# 8161_-FSK_V2_0.net
KiCad netlist of a schematic drawn in Altium Designer
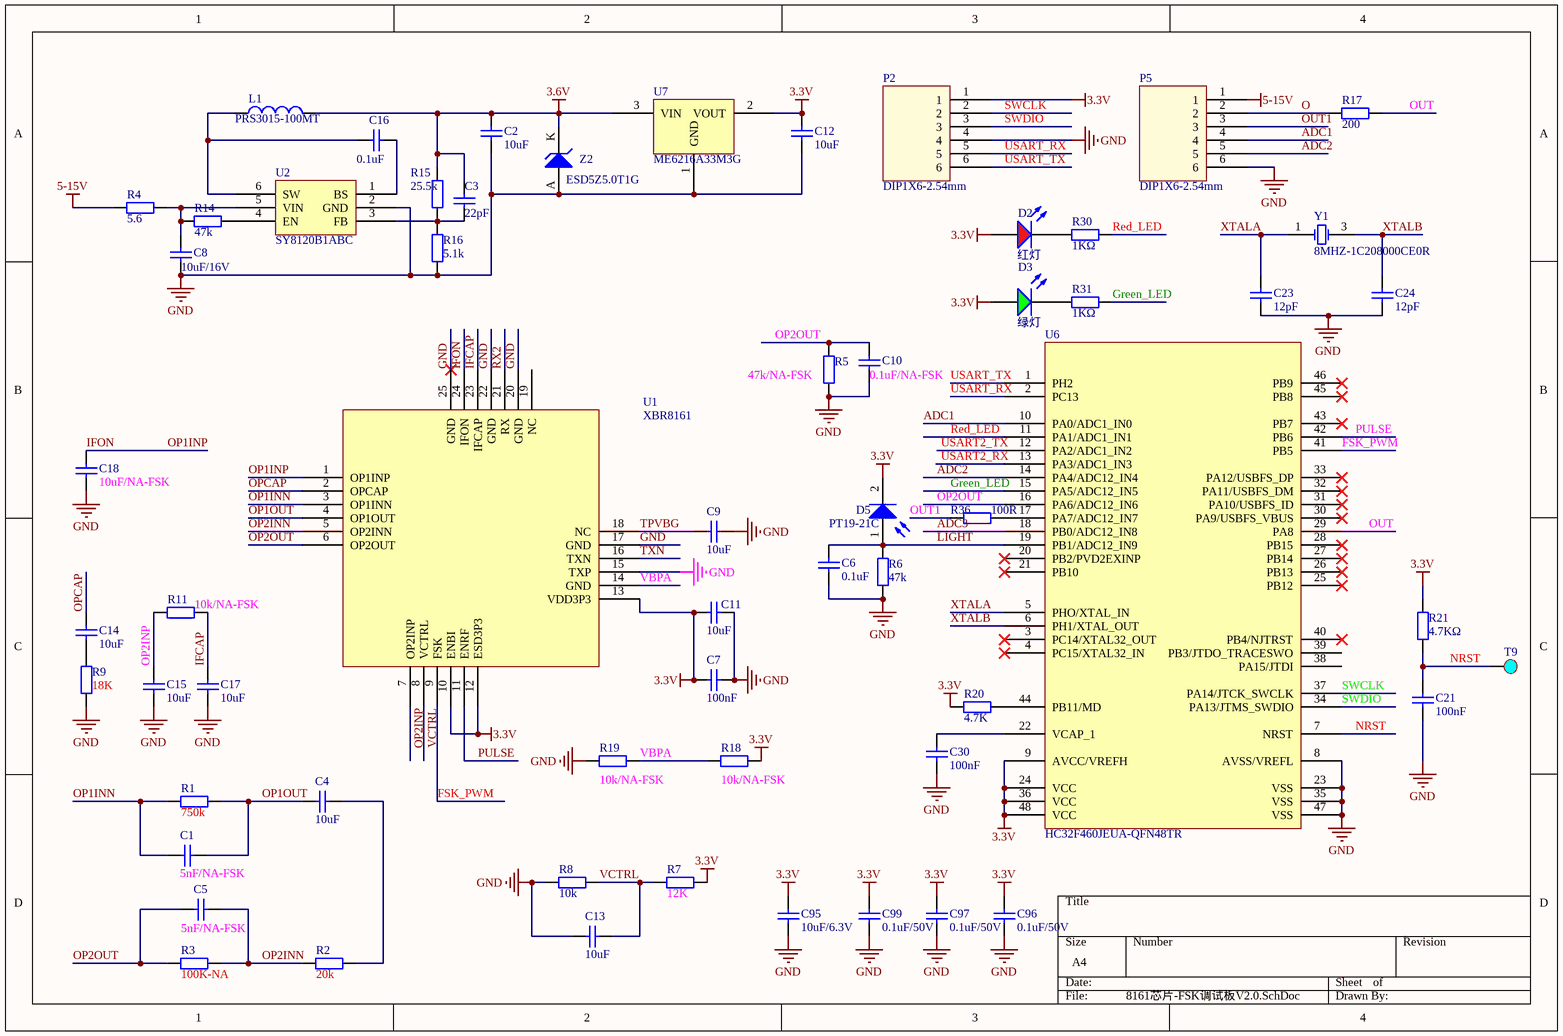
[diagram p0: 8161芯片-FSK调试板V2.0.SchDoc]

(export (version "E")
  (design (tool "Eeschema 10.0.6"))
  (components
    (comp (ref "C1")
      (value "5nF/NA-FSK")
      (footprint "C0402")
      (description "Capacitor")
      (fields (field (name "PUBLISHER") "Altium Limited"))
      (libsource (lib "Miscellaneous Devices") (part "Cap"))
    )
    (comp (ref "C2")
      (value "10uF")
      (footprint "C0402")
      (description "Capacitor")
      (fields (field (name "PUBLISHER") "Altium Limited"))
      (libsource (lib "Miscellaneous Devices") (part "Cap"))
    )
    (comp (ref "C3")
      (value "22pF")
      (footprint "C0402")
      (description "Capacitor")
      (fields (field (name "PUBLISHER") "Altium Limited"))
      (libsource (lib "Miscellaneous Devices") (part "Cap"))
    )
    (comp (ref "C4")
      (value "10uF")
      (footprint "C0402")
      (description "Capacitor")
      (fields (field (name "PUBLISHER") "Altium Limited"))
      (libsource (lib "Miscellaneous Devices") (part "Cap"))
    )
    (comp (ref "C5")
      (value "5nF/NA-FSK")
      (footprint "C0402")
      (description "Capacitor")
      (fields (field (name "PUBLISHER") "Altium Limited"))
      (libsource (lib "Miscellaneous Devices") (part "Cap"))
    )
    (comp (ref "C6")
      (value "0.1uF")
      (footprint "C0402")
      (description "Capacitor")
      (fields (field (name "PUBLISHER") "Altium Limited"))
      (libsource (lib "Miscellaneous Devices") (part "Cap"))
    )
    (comp (ref "C7")
      (value "100nF")
      (footprint "C0402")
      (description "Capacitor")
      (fields (field (name "PUBLISHER") "Altium Limited"))
      (libsource (lib "Miscellaneous Devices") (part "Cap"))
    )
    (comp (ref "C8")
      (value "10uF/16V")
      (footprint "C0603")
      (description "Capacitor")
      (fields (field (name "PUBLISHER") "Altium Limited"))
      (libsource (lib "Miscellaneous Devices") (part "Cap"))
    )
    (comp (ref "C9")
      (value "10uF")
      (footprint "C0402")
      (description "Capacitor")
      (fields (field (name "PUBLISHER") "Altium Limited"))
      (libsource (lib "Miscellaneous Devices") (part "Cap"))
    )
    (comp (ref "C10")
      (value "0.1uF/NA-FSK")
      (footprint "C0402")
      (description "Capacitor")
      (fields (field (name "PUBLISHER") "Altium Limited"))
      (libsource (lib "Miscellaneous Devices") (part "Cap"))
    )
    (comp (ref "C11")
      (value "10uF")
      (footprint "C0402")
      (description "Capacitor")
      (fields (field (name "PUBLISHER") "Altium Limited"))
      (libsource (lib "Miscellaneous Devices") (part "Cap"))
    )
    (comp (ref "C12")
      (value "10uF")
      (footprint "C0402")
      (description "Capacitor")
      (fields (field (name "PUBLISHER") "Altium Limited"))
      (libsource (lib "Miscellaneous Devices") (part "Cap"))
    )
    (comp (ref "C13")
      (value "10uF")
      (footprint "C0402")
      (description "Capacitor")
      (fields (field (name "PUBLISHER") "Altium Limited"))
      (libsource (lib "Miscellaneous Devices") (part "Cap"))
    )
    (comp (ref "C14")
      (value "10uF")
      (footprint "C0402")
      (description "Capacitor")
      (fields (field (name "PUBLISHER") "Altium Limited"))
      (libsource (lib "Miscellaneous Devices") (part "Cap"))
    )
    (comp (ref "C15")
      (value "10uF")
      (footprint "C0402")
      (description "Capacitor")
      (fields (field (name "PUBLISHER") "Altium Limited"))
      (libsource (lib "Miscellaneous Devices") (part "Cap"))
    )
    (comp (ref "C16")
      (value "0.1uF")
      (footprint "C0402")
      (description "Capacitor")
      (fields (field (name "PUBLISHER") "Altium Limited"))
      (libsource (lib "Miscellaneous Devices") (part "Cap"))
    )
    (comp (ref "C17")
      (value "10uF")
      (footprint "C0402")
      (description "Capacitor")
      (fields (field (name "PUBLISHER") "Altium Limited"))
      (libsource (lib "Miscellaneous Devices") (part "Cap"))
    )
    (comp (ref "C18")
      (value "10uF/NA-FSK")
      (footprint "C0402")
      (description "Capacitor")
      (fields (field (name "PUBLISHER") "Altium Limited"))
      (libsource (lib "Miscellaneous Devices") (part "Cap"))
    )
    (comp (ref "C21")
      (value "100nF")
      (footprint "C0402")
      (description "贴片电容")
      (libsource (lib "Miscellaneous Devices LC") (part "0402 100nF (104) 10% 16V"))
    )
    (comp (ref "C23")
      (value "12pF")
      (footprint "C0402")
      (description "贴片电容")
      (libsource (lib "Cap") (part "0402 22pF (220) 5% 50V"))
    )
    (comp (ref "C24")
      (value "12pF")
      (footprint "C0402")
      (description "贴片电容")
      (libsource (lib "Cap") (part "0402 22pF (220) 5% 50V"))
    )
    (comp (ref "C30")
      (value "100nF")
      (footprint "C0402")
      (description "Capacitor")
      (fields (field (name "PUBLISHER") "Altium Limited"))
      (libsource (lib "Miscellaneous Devices") (part "Cap"))
    )
    (comp (ref "C95")
      (value "10uF/6.3V")
      (footprint "C0402")
      (description "贴片电容")
      (libsource (lib "Cap") (part "0402 2.2nF (222) 10% 50V"))
    )
    (comp (ref "C96")
      (value "0.1uF/50V")
      (footprint "C0402")
      (description "贴片电容")
      (libsource (lib "Cap") (part "0402 2.2nF (222) 10% 50V"))
    )
    (comp (ref "C97")
      (value "0.1uF/50V")
      (footprint "C0402")
      (description "贴片电容")
      (libsource (lib "Cap") (part "0402 2.2nF (222) 10% 50V"))
    )
    (comp (ref "C99")
      (value "0.1uF/50V")
      (footprint "C0402")
      (description "贴片电容")
      (libsource (lib "Cap") (part "0402 2.2nF (222) 10% 50V"))
    )
    (comp (ref "D2")
      (value "红灯")
      (footprint "LC-0603_LED_S1")
      (description "发光二极管")
      (libsource (lib "Miscellaneous Devices LC") (part "0603 红灯"))
    )
    (comp (ref "D3")
      (value "绿灯")
      (footprint "LC-0603_LED_S1")
      (description "发光二极管")
      (libsource (lib "30x35雷达微动底板V0.2") (part "0603 红灯"))
    )
    (comp (ref "D5")
      (value "PT19-21C")
      (footprint "LED-0603")
      (description "Photosensitive Diode")
      (fields (field (name "PUBLISHER") "Altium Limited"))
      (libsource (lib "Miscellaneous Devices") (part "Photo Sen"))
    )
    (comp (ref "L1")
      (value "PRS3015-100MT")
      (footprint "PRS3015")
      (description "Inductor")
      (fields (field (name "PUBLISHER") "Altium Limited"))
      (libsource (lib "Miscellaneous Devices") (part "Inductor"))
    )
    (comp (ref "P2")
      (value "DIP1X6-2.54mm")
      (footprint "DIP1X6-2.54")
      (libsource (lib "30x35雷达微动底板V0.2") (part "DIP1X6-2.54mm"))
    )
    (comp (ref "P5")
      (value "DIP1X6-2.54mm")
      (footprint "DIP1X6-2.54")
      (libsource (lib "30x35雷达微动底板V0.2") (part "DIP1X6-2.54mm"))
    )
    (comp (ref "R1")
      (value "750k")
      (footprint "R0402")
      (description "Resistor")
      (fields (field (name "PUBLISHER") "Altium Limited"))
      (libsource (lib "") (part "Res2_4"))
    )
    (comp (ref "R2")
      (value "20k")
      (footprint "R0402")
      (description "Resistor")
      (fields (field (name "PUBLISHER") "Altium Limited"))
      (libsource (lib "") (part "Res2_1"))
    )
    (comp (ref "R3")
      (value "100K-NA")
      (footprint "R0402")
      (description "Resistor")
      (fields (field (name "PUBLISHER") "Altium Limited"))
      (libsource (lib "") (part "Res2_1"))
    )
    (comp (ref "R4")
      (value "5.6")
      (footprint "R0402")
      (description "Resistor")
      (fields (field (name "PUBLISHER") "Altium Limited"))
      (libsource (lib "") (part "Res2_3"))
    )
    (comp (ref "R5")
      (value "47k/NA-FSK")
      (footprint "R0402")
      (description "Resistor")
      (fields (field (name "PUBLISHER") "Altium Limited"))
      (libsource (lib "Miscellaneous Devices") (part "Res2"))
    )
    (comp (ref "R6")
      (value "47k")
      (footprint "R0402")
      (description "Resistor")
      (fields (field (name "PUBLISHER") "Altium Limited"))
      (libsource (lib "Miscellaneous Devices") (part "Res2"))
    )
    (comp (ref "R7")
      (value "12K")
      (footprint "R0402")
      (description "Resistor")
      (fields (field (name "PUBLISHER") "Altium Limited"))
      (libsource (lib "") (part "Res2_1"))
    )
    (comp (ref "R8")
      (value "10k")
      (footprint "R0402")
      (description "Resistor")
      (fields (field (name "PUBLISHER") "Altium Limited"))
      (libsource (lib "") (part "Res2_1"))
    )
    (comp (ref "R9")
      (value "18K")
      (footprint "R0402")
      (description "Resistor")
      (fields (field (name "PUBLISHER") "Altium Limited"))
      (libsource (lib "Miscellaneous Devices") (part "Res2"))
    )
    (comp (ref "R11")
      (value "10k/NA-FSK")
      (footprint "R0402")
      (description "Resistor")
      (fields (field (name "PUBLISHER") "Altium Limited"))
      (libsource (lib "") (part "Res2_1"))
    )
    (comp (ref "R14")
      (value "47k")
      (footprint "R0402")
      (description "Resistor")
      (fields (field (name "PUBLISHER") "Altium Limited"))
      (libsource (lib "") (part "Res2_1"))
    )
    (comp (ref "R15")
      (value "25.5k")
      (footprint "R0402")
      (description "Resistor")
      (fields (field (name "PUBLISHER") "Altium Limited"))
      (libsource (lib "") (part "Res2_2"))
    )
    (comp (ref "R16")
      (value "5.1k")
      (footprint "R0402")
      (description "Resistor")
      (fields (field (name "PUBLISHER") "Altium Limited"))
      (libsource (lib "") (part "Res2_2"))
    )
    (comp (ref "R17")
      (value "200")
      (footprint "R0402")
      (description "Resistor")
      (fields (field (name "PUBLISHER") "Altium Limited"))
      (libsource (lib "") (part "Res2_4"))
    )
    (comp (ref "R18")
      (value "10k/NA-FSK")
      (footprint "R0402")
      (description "Resistor")
      (fields (field (name "PUBLISHER") "Altium Limited"))
      (libsource (lib "") (part "Res2_1"))
    )
    (comp (ref "R19")
      (value "10k/NA-FSK")
      (footprint "R0402")
      (description "Resistor")
      (fields (field (name "PUBLISHER") "Altium Limited"))
      (libsource (lib "") (part "Res2_1"))
    )
    (comp (ref "R20")
      (value "4.7K")
      (footprint "R0402")
      (description "Resistor")
      (fields (field (name "PUBLISHER") "Altium Limited"))
      (libsource (lib "") (part "Res2_4"))
    )
    (comp (ref "R21")
      (value "4.7KΩ")
      (footprint "R0402")
      (description "贴片电阻")
      (libsource (lib "Miscellaneous Devices LC") (part "0402 4.7KΩ (4701) 1%"))
    )
    (comp (ref "R30")
      (value "1KΩ")
      (footprint "R0402")
      (description "贴片电阻")
      (libsource (lib "Miscellaneous Devices LC") (part "0402 1KΩ (1001) 1%"))
    )
    (comp (ref "R31")
      (value "1KΩ")
      (footprint "R0402")
      (description "贴片电阻")
      (libsource (lib "Miscellaneous Devices LC") (part "0402 1KΩ (1001) 1%"))
    )
    (comp (ref "R36")
      (value "100R")
      (footprint "R0402")
      (description "贴片电阻")
      (libsource (lib "") (part "0402 4.7KΩ (4701) 1%_1"))
    )
    (comp (ref "T9")
      (value "~")
      (footprint "TestPoints")
      (description "TestPoints")
      (libsource (lib "标准原理图库（特种板）") (part "TestPoints"))
    )
    (comp (ref "U1")
      (value "XBR8161")
      (footprint "QFN24")
      (libsource (lib "altium-import") (part "root_0_XBR8161_"))
    )
    (comp (ref "U2") (value "SY8120B1ABC") (footprint "SOT-23-6") (libsource (lib "Schlib1") (part "H9108")))
    (comp (ref "U6")
      (value "HC32F460JEUA-QFN48TR")
      (footprint "QFN48-5X5mm")
      (libsource (lib "LD-ShouShi-Module-V1.0") (part "HC32F460JETA-LQFP48"))
    )
    (comp (ref "U7")
      (value "ME6216A33M3G")
      (footprint "SOT-23-L")
      (libsource (lib "Schlib1") (part "SSP6206"))
    )
    (comp (ref "Y1")
      (value "8MHZ-1C208000CE0R")
      (footprint "OSC-SMD_3225")
      (description "贴片晶振")
      (libsource (lib "CrystalOscillator") (part "SMD-3225_4P  25MHZ 12PF 10PPM"))
    )
    (comp (ref "Z2")
      (value "ESD5Z5.0T1G")
      (footprint "SOD323")
      (description "Zener Diode")
      (fields (field (name "PUBLISHER") "Altium Limited"))
      (libsource (lib "Miscellaneous Devices") (part "D Zener"))
    )
  )
  (nets
    (net (code "1") (name "/ADC1") (class "Default")
      (node (ref "P5") (pin "4") (pinfunction "4_4") (pintype "passive"))
      (node (ref "U6") (pin "10") (pinfunction "PA0/ADC1_IN0_10") (pintype "passive"))
    )
    (net (code "2") (name "/ADC2") (class "Default")
      (node (ref "P5") (pin "5") (pinfunction "5_5") (pintype "passive"))
      (node (ref "U6") (pin "14") (pinfunction "PA4/ADC12_IN4_14") (pintype "passive"))
    )
    (net (code "3") (name "/ADC3") (class "Default")
      (node (ref "U6") (pin "18") (pinfunction "PB0/ADC12_IN8_18") (pintype "passive"))
    )
    (net (code "4") (name "/FSK_PWM") (class "Default")
      (node (ref "U1") (pin "9") (pinfunction "FSK_9") (pintype "passive"))
      (node (ref "U6") (pin "41") (pinfunction "PB5_41") (pintype "passive"))
    )
    (net (code "5") (name "/Green_LED") (class "Default")
      (node (ref "R31") (pin "1") (pinfunction "1_1") (pintype "passive"))
      (node (ref "U6") (pin "15") (pinfunction "PA5/ADC12_IN5_15") (pintype "passive"))
    )
    (net (code "6") (name "/IFCAP") (class "Default")
      (node (ref "C17") (pin "2") (pinfunction "2_2") (pintype "passive"))
      (node (ref "R11") (pin "1") (pinfunction "1_1") (pintype "passive"))
      (node (ref "U1") (pin "23") (pinfunction "IFCAP_23") (pintype "passive"))
    )
    (net (code "7") (name "/IFON") (class "Default")
      (node (ref "C18") (pin "2") (pinfunction "2_2") (pintype "passive"))
      (node (ref "U1") (pin "1") (pinfunction "OP1INP_1") (pintype "passive"))
      (node (ref "U1") (pin "24") (pinfunction "IFON_24") (pintype "passive"))
    )
    (net (code "8") (name "/LIGHT") (class "Default")
      (node (ref "C6") (pin "1") (pinfunction "1_1") (pintype "passive"))
      (node (ref "D5") (pin "1") (pinfunction "A_1") (pintype "passive"))
      (node (ref "R6") (pin "1") (pinfunction "1_1") (pintype "passive"))
      (node (ref "U6") (pin "19") (pinfunction "PB1/ADC12_IN9_19") (pintype "passive"))
    )
    (net (code "9") (name "/NRST") (class "Default")
      (node (ref "C21") (pin "2") (pinfunction "2_2") (pintype "passive"))
      (node (ref "R21") (pin "1") (pinfunction "1_1") (pintype "passive"))
      (node (ref "T9") (pin "1") (pinfunction "1_1") (pintype "passive"))
      (node (ref "U6") (pin "7") (pinfunction "NRST_7") (pintype "passive"))
    )
    (net (code "10") (name "/O") (class "Default")
      (node (ref "P5") (pin "2") (pinfunction "2_2") (pintype "passive"))
      (node (ref "R17") (pin "1") (pinfunction "1_1") (pintype "passive"))
    )
    (net (code "11") (name "/OP1INN") (class "Default")
      (node (ref "C1") (pin "2") (pinfunction "2_2") (pintype "passive"))
      (node (ref "R1") (pin "1") (pinfunction "1_1") (pintype "passive"))
      (node (ref "U1") (pin "3") (pinfunction "OP1INN_3") (pintype "passive"))
    )
    (net (code "12") (name "/OP1OUT") (class "Default")
      (node (ref "C1") (pin "1") (pinfunction "1_1") (pintype "passive"))
      (node (ref "C4") (pin "2") (pinfunction "2_2") (pintype "passive"))
      (node (ref "R1") (pin "2") (pinfunction "2_2") (pintype "passive"))
      (node (ref "U1") (pin "4") (pinfunction "OP1OUT_4") (pintype "passive"))
    )
    (net (code "13") (name "/OP2INN") (class "Default")
      (node (ref "C5") (pin "2") (pinfunction "2_2") (pintype "passive"))
      (node (ref "R2") (pin "2") (pinfunction "2_2") (pintype "passive"))
      (node (ref "R3") (pin "1") (pinfunction "1_1") (pintype "passive"))
      (node (ref "U1") (pin "5") (pinfunction "OP2INN_5") (pintype "passive"))
    )
    (net (code "14") (name "/OP2INP") (class "Default")
      (node (ref "C15") (pin "1") (pinfunction "1_1") (pintype "passive"))
      (node (ref "R11") (pin "2") (pinfunction "2_2") (pintype "passive"))
      (node (ref "U1") (pin "7") (pinfunction "OP2INP_7") (pintype "passive"))
    )
    (net (code "15") (name "/OP2OUT") (class "Default")
      (node (ref "C10") (pin "1") (pinfunction "1_1") (pintype "passive"))
      (node (ref "C5") (pin "1") (pinfunction "1_1") (pintype "passive"))
      (node (ref "R3") (pin "2") (pinfunction "2_2") (pintype "passive"))
      (node (ref "R5") (pin "1") (pinfunction "1_1") (pintype "passive"))
      (node (ref "U1") (pin "6") (pinfunction "OP2OUT_6") (pintype "passive"))
      (node (ref "U6") (pin "16") (pinfunction "PA6/ADC12_IN6_16") (pintype "passive"))
    )
    (net (code "16") (name "/OPCAP") (class "Default")
      (node (ref "C14") (pin "2") (pinfunction "2_2") (pintype "passive"))
      (node (ref "U1") (pin "2") (pinfunction "OPCAP_2") (pintype "passive"))
    )
    (net (code "17") (name "/OUT") (class "Default")
      (node (ref "R17") (pin "2") (pinfunction "2_2") (pintype "passive"))
      (node (ref "U6") (pin "29") (pinfunction "PA8_29") (pintype "passive"))
    )
    (net (code "18") (name "/OUT1") (class "Default")
      (node (ref "P5") (pin "3") (pinfunction "3_3") (pintype "passive"))
      (node (ref "R36") (pin "2") (pinfunction "2_2") (pintype "passive"))
    )
    (net (code "19") (name "/PULSE") (class "Default")
      (node (ref "U1") (pin "11") (pinfunction "ENRF_11") (pintype "passive"))
      (node (ref "U6") (pin "42") (pinfunction "PB6_42") (pintype "passive"))
    )
    (net (code "20") (name "/RX2") (class "Default")
      (node (ref "U1") (pin "21") (pinfunction "RX_21") (pintype "passive"))
    )
    (net (code "21") (name "/Red_LED") (class "Default")
      (node (ref "R30") (pin "1") (pinfunction "1_1") (pintype "passive"))
      (node (ref "U6") (pin "11") (pinfunction "PA1/ADC1_IN1_11") (pintype "passive"))
    )
    (net (code "22") (name "/SWCLK") (class "Default")
      (node (ref "P2") (pin "2") (pinfunction "2_2") (pintype "passive"))
      (node (ref "U6") (pin "37") (pinfunction "PA14/JTCK_SWCLK_37") (pintype "passive"))
    )
    (net (code "23") (name "/SWDIO") (class "Default")
      (node (ref "P2") (pin "3") (pinfunction "3_3") (pintype "passive"))
      (node (ref "U6") (pin "34") (pinfunction "PA13/JTMS_SWDIO_34") (pintype "passive"))
    )
    (net (code "24") (name "/TPVBG") (class "Default")
      (node (ref "C9") (pin "2") (pinfunction "2_2") (pintype "passive"))
      (node (ref "U1") (pin "18") (pinfunction "NC_18") (pintype "passive"))
    )
    (net (code "25") (name "/TXN") (class "Default")
      (node (ref "U1") (pin "16") (pinfunction "TXN_16") (pintype "passive"))
    )
    (net (code "26") (name "/USART2_RX") (class "Default")
      (node (ref "U6") (pin "13") (pinfunction "PA3/ADC1_IN3_13") (pintype "passive"))
    )
    (net (code "27") (name "/USART2_TX") (class "Default")
      (node (ref "U6") (pin "12") (pinfunction "PA2/ADC1_IN2_12") (pintype "passive"))
    )
    (net (code "28") (name "/USART_RX") (class "Default")
      (node (ref "P2") (pin "5") (pinfunction "5_5") (pintype "passive"))
      (node (ref "U6") (pin "2") (pinfunction "PC13_2") (pintype "passive"))
    )
    (net (code "29") (name "/USART_TX") (class "Default")
      (node (ref "P2") (pin "6") (pinfunction "6_6") (pintype "passive"))
      (node (ref "U6") (pin "1") (pinfunction "PH2_1") (pintype "passive"))
    )
    (net (code "30") (name "/VBPA") (class "Default")
      (node (ref "R18") (pin "2") (pinfunction "2_2") (pintype "passive"))
      (node (ref "R19") (pin "1") (pinfunction "1_1") (pintype "passive"))
      (node (ref "U1") (pin "14") (pinfunction "GND_14") (pintype "passive"))
    )
    (net (code "31") (name "/VCTRL") (class "Default")
      (node (ref "C13") (pin "1") (pinfunction "1_1") (pintype "passive"))
      (node (ref "R7") (pin "2") (pinfunction "2_2") (pintype "passive"))
      (node (ref "R8") (pin "1") (pinfunction "1_1") (pintype "passive"))
      (node (ref "U1") (pin "8") (pinfunction "VCTRL_8") (pintype "passive"))
    )
    (net (code "32") (name "/XTALA") (class "Default")
      (node (ref "C23") (pin "2") (pinfunction "2_2") (pintype "passive"))
      (node (ref "U6") (pin "5") (pinfunction "PHO/XTAL_IN_5") (pintype "passive"))
      (node (ref "Y1") (pin "1") (pinfunction "OSC1_1") (pintype "passive"))
    )
    (net (code "33") (name "/XTALB") (class "Default")
      (node (ref "C24") (pin "2") (pinfunction "2_2") (pintype "passive"))
      (node (ref "U6") (pin "6") (pinfunction "PH1/XTAL_OUT_6") (pintype "passive"))
      (node (ref "Y1") (pin "3") (pinfunction "OSC2_3") (pintype "passive"))
    )
    (net (code "34") (name "3.3V") (class "Default")
      (node (ref "C11") (pin "2") (pinfunction "2_2") (pintype "passive"))
      (node (ref "C12") (pin "1") (pinfunction "1_1") (pintype "passive"))
      (node (ref "C7") (pin "2") (pinfunction "2_2") (pintype "passive"))
      (node (ref "C95") (pin "1") (pinfunction "1_1") (pintype "passive"))
      (node (ref "C96") (pin "1") (pinfunction "1_1") (pintype "passive"))
      (node (ref "C97") (pin "1") (pinfunction "1_1") (pintype "passive"))
      (node (ref "C99") (pin "1") (pinfunction "1_1") (pintype "passive"))
      (node (ref "D2") (pin "A") (pinfunction "A_A") (pintype "passive"))
      (node (ref "D3") (pin "A") (pinfunction "A_A") (pintype "passive"))
      (node (ref "D5") (pin "2") (pinfunction "K_2") (pintype "passive"))
      (node (ref "P2") (pin "1") (pinfunction "1_1") (pintype "passive"))
      (node (ref "R18") (pin "1") (pinfunction "1_1") (pintype "passive"))
      (node (ref "R20") (pin "1") (pinfunction "1_1") (pintype "passive"))
      (node (ref "R21") (pin "2") (pinfunction "2_2") (pintype "passive"))
      (node (ref "R7") (pin "1") (pinfunction "1_1") (pintype "passive"))
      (node (ref "U1") (pin "10") (pinfunction "ENBI_10") (pintype "passive"))
      (node (ref "U1") (pin "12") (pinfunction "ESD3P3_12") (pintype "passive"))
      (node (ref "U1") (pin "13") (pinfunction "VDD3P3_13") (pintype "passive"))
      (node (ref "U6") (pin "24") (pinfunction "VCC_24") (pintype "passive"))
      (node (ref "U6") (pin "36") (pinfunction "VCC_36") (pintype "passive"))
      (node (ref "U6") (pin "48") (pinfunction "VCC_48") (pintype "passive"))
      (node (ref "U6") (pin "9") (pinfunction "AVCC/VREFH_9") (pintype "passive"))
      (node (ref "U7") (pin "2") (pinfunction "VOUT_2") (pintype "passive"))
    )
    (net (code "35") (name "3.6V") (class "Default")
      (node (ref "C2") (pin "1") (pinfunction "1_1") (pintype "passive"))
      (node (ref "C3") (pin "2") (pinfunction "2_2") (pintype "passive"))
      (node (ref "L1") (pin "2") (pinfunction "2_2") (pintype "passive"))
      (node (ref "R15") (pin "2") (pinfunction "2_2") (pintype "passive"))
      (node (ref "U7") (pin "3") (pinfunction "VIN_3") (pintype "passive"))
      (node (ref "Z2") (pin "K") (pinfunction "K_K") (pintype "passive"))
    )
    (net (code "36") (name "5-15V") (class "Default")
      (node (ref "P5") (pin "1") (pinfunction "1_1") (pintype "passive"))
      (node (ref "R4") (pin "1") (pinfunction "1_1") (pintype "passive"))
    )
    (net (code "37") (name "GND") (class "Default")
      (node (ref "C10") (pin "2") (pinfunction "2_2") (pintype "passive"))
      (node (ref "C11") (pin "1") (pinfunction "1_1") (pintype "passive"))
      (node (ref "C12") (pin "2") (pinfunction "2_2") (pintype "passive"))
      (node (ref "C13") (pin "2") (pinfunction "2_2") (pintype "passive"))
      (node (ref "C15") (pin "2") (pinfunction "2_2") (pintype "passive"))
      (node (ref "C17") (pin "1") (pinfunction "1_1") (pintype "passive"))
      (node (ref "C18") (pin "1") (pinfunction "1_1") (pintype "passive"))
      (node (ref "C2") (pin "2") (pinfunction "2_2") (pintype "passive"))
      (node (ref "C21") (pin "1") (pinfunction "1_1") (pintype "passive"))
      (node (ref "C23") (pin "1") (pinfunction "1_1") (pintype "passive"))
      (node (ref "C24") (pin "1") (pinfunction "1_1") (pintype "passive"))
      (node (ref "C30") (pin "2") (pinfunction "2_2") (pintype "passive"))
      (node (ref "C6") (pin "2") (pinfunction "2_2") (pintype "passive"))
      (node (ref "C7") (pin "1") (pinfunction "1_1") (pintype "passive"))
      (node (ref "C8") (pin "2") (pinfunction "2_2") (pintype "passive"))
      (node (ref "C9") (pin "1") (pinfunction "1_1") (pintype "passive"))
      (node (ref "C95") (pin "2") (pinfunction "2_2") (pintype "passive"))
      (node (ref "C96") (pin "2") (pinfunction "2_2") (pintype "passive"))
      (node (ref "C97") (pin "2") (pinfunction "2_2") (pintype "passive"))
      (node (ref "C99") (pin "2") (pinfunction "2_2") (pintype "passive"))
      (node (ref "P2") (pin "4") (pinfunction "4_4") (pintype "passive"))
      (node (ref "P5") (pin "6") (pinfunction "6_6") (pintype "passive"))
      (node (ref "R16") (pin "1") (pinfunction "1_1") (pintype "passive"))
      (node (ref "R19") (pin "2") (pinfunction "2_2") (pintype "passive"))
      (node (ref "R5") (pin "2") (pinfunction "2_2") (pintype "passive"))
      (node (ref "R6") (pin "2") (pinfunction "2_2") (pintype "passive"))
      (node (ref "R8") (pin "2") (pinfunction "2_2") (pintype "passive"))
      (node (ref "R9") (pin "2") (pinfunction "2_2") (pintype "passive"))
      (node (ref "U1") (pin "15") (pinfunction "TXP_15") (pintype "passive"))
      (node (ref "U1") (pin "17") (pinfunction "GND_17") (pintype "passive"))
      (node (ref "U1") (pin "20") (pinfunction "GND_20") (pintype "passive"))
      (node (ref "U1") (pin "22") (pinfunction "GND_22") (pintype "passive"))
      (node (ref "U1") (pin "25") (pinfunction "GND_25") (pintype "passive"))
      (node (ref "U2") (pin "2") (pinfunction "GND_2") (pintype "passive"))
      (node (ref "U6") (pin "23") (pinfunction "VSS_23") (pintype "passive"))
      (node (ref "U6") (pin "35") (pinfunction "VSS_35") (pintype "passive"))
      (node (ref "U6") (pin "47") (pinfunction "VSS_47") (pintype "passive"))
      (node (ref "U6") (pin "8") (pinfunction "AVSS/VREFL_8") (pintype "passive"))
      (node (ref "U7") (pin "1") (pinfunction "GND_1") (pintype "passive"))
      (node (ref "Z2") (pin "A") (pinfunction "A_A") (pintype "passive"))
    )
    (net (code "38") (name "Net-(C4-Pad1)") (class "Default")
      (node (ref "C4") (pin "1") (pinfunction "1_1") (pintype "passive"))
      (node (ref "R2") (pin "1") (pinfunction "1_1") (pintype "passive"))
    )
    (net (code "39") (name "Net-(C14-Pad1)") (class "Default")
      (node (ref "C14") (pin "1") (pinfunction "1_1") (pintype "passive"))
      (node (ref "R9") (pin "1") (pinfunction "1_1") (pintype "passive"))
    )
    (net (code "40") (name "Net-(D2-PadK)") (class "Default")
      (node (ref "D2") (pin "K") (pinfunction "K_K") (pintype "passive"))
      (node (ref "R30") (pin "2") (pinfunction "2_2") (pintype "passive"))
    )
    (net (code "41") (name "Net-(D3-PadK)") (class "Default")
      (node (ref "D3") (pin "K") (pinfunction "K_K") (pintype "passive"))
      (node (ref "R31") (pin "2") (pinfunction "2_2") (pintype "passive"))
    )
    (net (code "42") (name "Net-(U2-BS)") (class "Default")
      (node (ref "C16") (pin "2") (pinfunction "2_2") (pintype "passive"))
      (node (ref "U2") (pin "1") (pinfunction "BS_1") (pintype "passive"))
    )
    (net (code "43") (name "Net-(U2-EN)") (class "Default")
      (node (ref "R14") (pin "1") (pinfunction "1_1") (pintype "passive"))
      (node (ref "U2") (pin "4") (pinfunction "EN_4") (pintype "passive"))
    )
    (net (code "44") (name "Net-(U2-FB)") (class "Default")
      (node (ref "C3") (pin "1") (pinfunction "1_1") (pintype "passive"))
      (node (ref "R15") (pin "1") (pinfunction "1_1") (pintype "passive"))
      (node (ref "R16") (pin "2") (pinfunction "2_2") (pintype "passive"))
      (node (ref "U2") (pin "3") (pinfunction "FB_3") (pintype "passive"))
    )
    (net (code "45") (name "Net-(U2-SW)") (class "Default")
      (node (ref "C16") (pin "1") (pinfunction "1_1") (pintype "passive"))
      (node (ref "L1") (pin "1") (pinfunction "1_1") (pintype "passive"))
      (node (ref "U2") (pin "6") (pinfunction "SW_6") (pintype "passive"))
    )
    (net (code "46") (name "Net-(U2-VIN)") (class "Default")
      (node (ref "C8") (pin "1") (pinfunction "1_1") (pintype "passive"))
      (node (ref "R14") (pin "2") (pinfunction "2_2") (pintype "passive"))
      (node (ref "R4") (pin "2") (pinfunction "2_2") (pintype "passive"))
      (node (ref "U2") (pin "5") (pinfunction "VIN_5") (pintype "passive"))
    )
    (net (code "47") (name "Net-(U6-PA7{slash}ADC12_IN7)") (class "Default")
      (node (ref "R36") (pin "1") (pinfunction "1_1") (pintype "passive"))
      (node (ref "U6") (pin "17") (pinfunction "PA7/ADC12_IN7_17") (pintype "passive"))
    )
    (net (code "48") (name "Net-(U6-PB11{slash}MD)") (class "Default")
      (node (ref "R20") (pin "2") (pinfunction "2_2") (pintype "passive"))
      (node (ref "U6") (pin "44") (pinfunction "PB11/MD_44") (pintype "passive"))
    )
    (net (code "49") (name "Net-(U6-VCAP_1)") (class "Default")
      (node (ref "C30") (pin "1") (pinfunction "1_1") (pintype "passive"))
      (node (ref "U6") (pin "22") (pinfunction "VCAP_1_22") (pintype "passive"))
    )
    (net (code "50") (name "unconnected-(U1-NC-Pad19)") (class "Default")
      (node (ref "U1") (pin "19") (pinfunction "NC_19") (pintype "passive"))
    )
    (net (code "51") (name "unconnected-(U6-PA9{slash}USBFS_VBUS-Pad30)") (class "Default")
      (node (ref "U6") (pin "30") (pinfunction "PA9/USBFS_VBUS_30") (pintype "passive+no_connect"))
    )
    (net (code "52") (name "unconnected-(U6-PA10{slash}USBFS_ID-Pad31)") (class "Default")
      (node (ref "U6") (pin "31") (pinfunction "PA10/USBFS_ID_31") (pintype "passive+no_connect"))
    )
    (net (code "53") (name "unconnected-(U6-PA11{slash}USBFS_DM-Pad32)") (class "Default")
      (node (ref "U6") (pin "32") (pinfunction "PA11/USBFS_DM_32") (pintype "passive+no_connect"))
    )
    (net (code "54") (name "unconnected-(U6-PA12{slash}USBFS_DP-Pad33)") (class "Default")
      (node (ref "U6") (pin "33") (pinfunction "PA12/USBFS_DP_33") (pintype "passive+no_connect"))
    )
    (net (code "55") (name "unconnected-(U6-PA15{slash}JTDI-Pad38)") (class "Default")
      (node (ref "U6") (pin "38") (pinfunction "PA15/JTDI_38") (pintype "passive"))
    )
    (net (code "56") (name "unconnected-(U6-PB2{slash}PVD2EXINP-Pad20)") (class "Default")
      (node (ref "U6") (pin "20") (pinfunction "PB2/PVD2EXINP_20") (pintype "passive+no_connect"))
    )
    (net (code "57") (name "unconnected-(U6-PB3{slash}JTDO_TRACESWO-Pad39)") (class "Default")
      (node (ref "U6") (pin "39") (pinfunction "PB3/JTDO_TRACESWO_39") (pintype "passive"))
    )
    (net (code "58") (name "unconnected-(U6-PB4{slash}NJTRST-Pad40)") (class "Default")
      (node (ref "U6") (pin "40") (pinfunction "PB4/NJTRST_40") (pintype "passive+no_connect"))
    )
    (net (code "59") (name "unconnected-(U6-PB7-Pad43)") (class "Default")
      (node (ref "U6") (pin "43") (pinfunction "PB7_43") (pintype "passive+no_connect"))
    )
    (net (code "60") (name "unconnected-(U6-PB8-Pad45)") (class "Default")
      (node (ref "U6") (pin "45") (pinfunction "PB8_45") (pintype "passive+no_connect"))
    )
    (net (code "61") (name "unconnected-(U6-PB9-Pad46)") (class "Default")
      (node (ref "U6") (pin "46") (pinfunction "PB9_46") (pintype "passive+no_connect"))
    )
    (net (code "62") (name "unconnected-(U6-PB10-Pad21)") (class "Default")
      (node (ref "U6") (pin "21") (pinfunction "PB10_21") (pintype "passive+no_connect"))
    )
    (net (code "63") (name "unconnected-(U6-PB12-Pad25)") (class "Default")
      (node (ref "U6") (pin "25") (pinfunction "PB12_25") (pintype "passive+no_connect"))
    )
    (net (code "64") (name "unconnected-(U6-PB13-Pad26)") (class "Default")
      (node (ref "U6") (pin "26") (pinfunction "PB13_26") (pintype "passive+no_connect"))
    )
    (net (code "65") (name "unconnected-(U6-PB14-Pad27)") (class "Default")
      (node (ref "U6") (pin "27") (pinfunction "PB14_27") (pintype "passive+no_connect"))
    )
    (net (code "66") (name "unconnected-(U6-PB15-Pad28)") (class "Default")
      (node (ref "U6") (pin "28") (pinfunction "PB15_28") (pintype "passive+no_connect"))
    )
    (net (code "67") (name "unconnected-(U6-PC14{slash}XTAL32_OUT-Pad3)") (class "Default")
      (node (ref "U6") (pin "3") (pinfunction "PC14/XTAL32_OUT_3") (pintype "passive+no_connect"))
    )
    (net (code "68") (name "unconnected-(U6-PC15{slash}XTAL32_IN-Pad4)") (class "Default")
      (node (ref "U6") (pin "4") (pinfunction "PC15/XTAL32_IN_4") (pintype "passive+no_connect"))
    )
  )
)
